# kiibohd_at90usb_ext_i2c_l.net
KiCad netlist of a schematic drawn in EAGLE
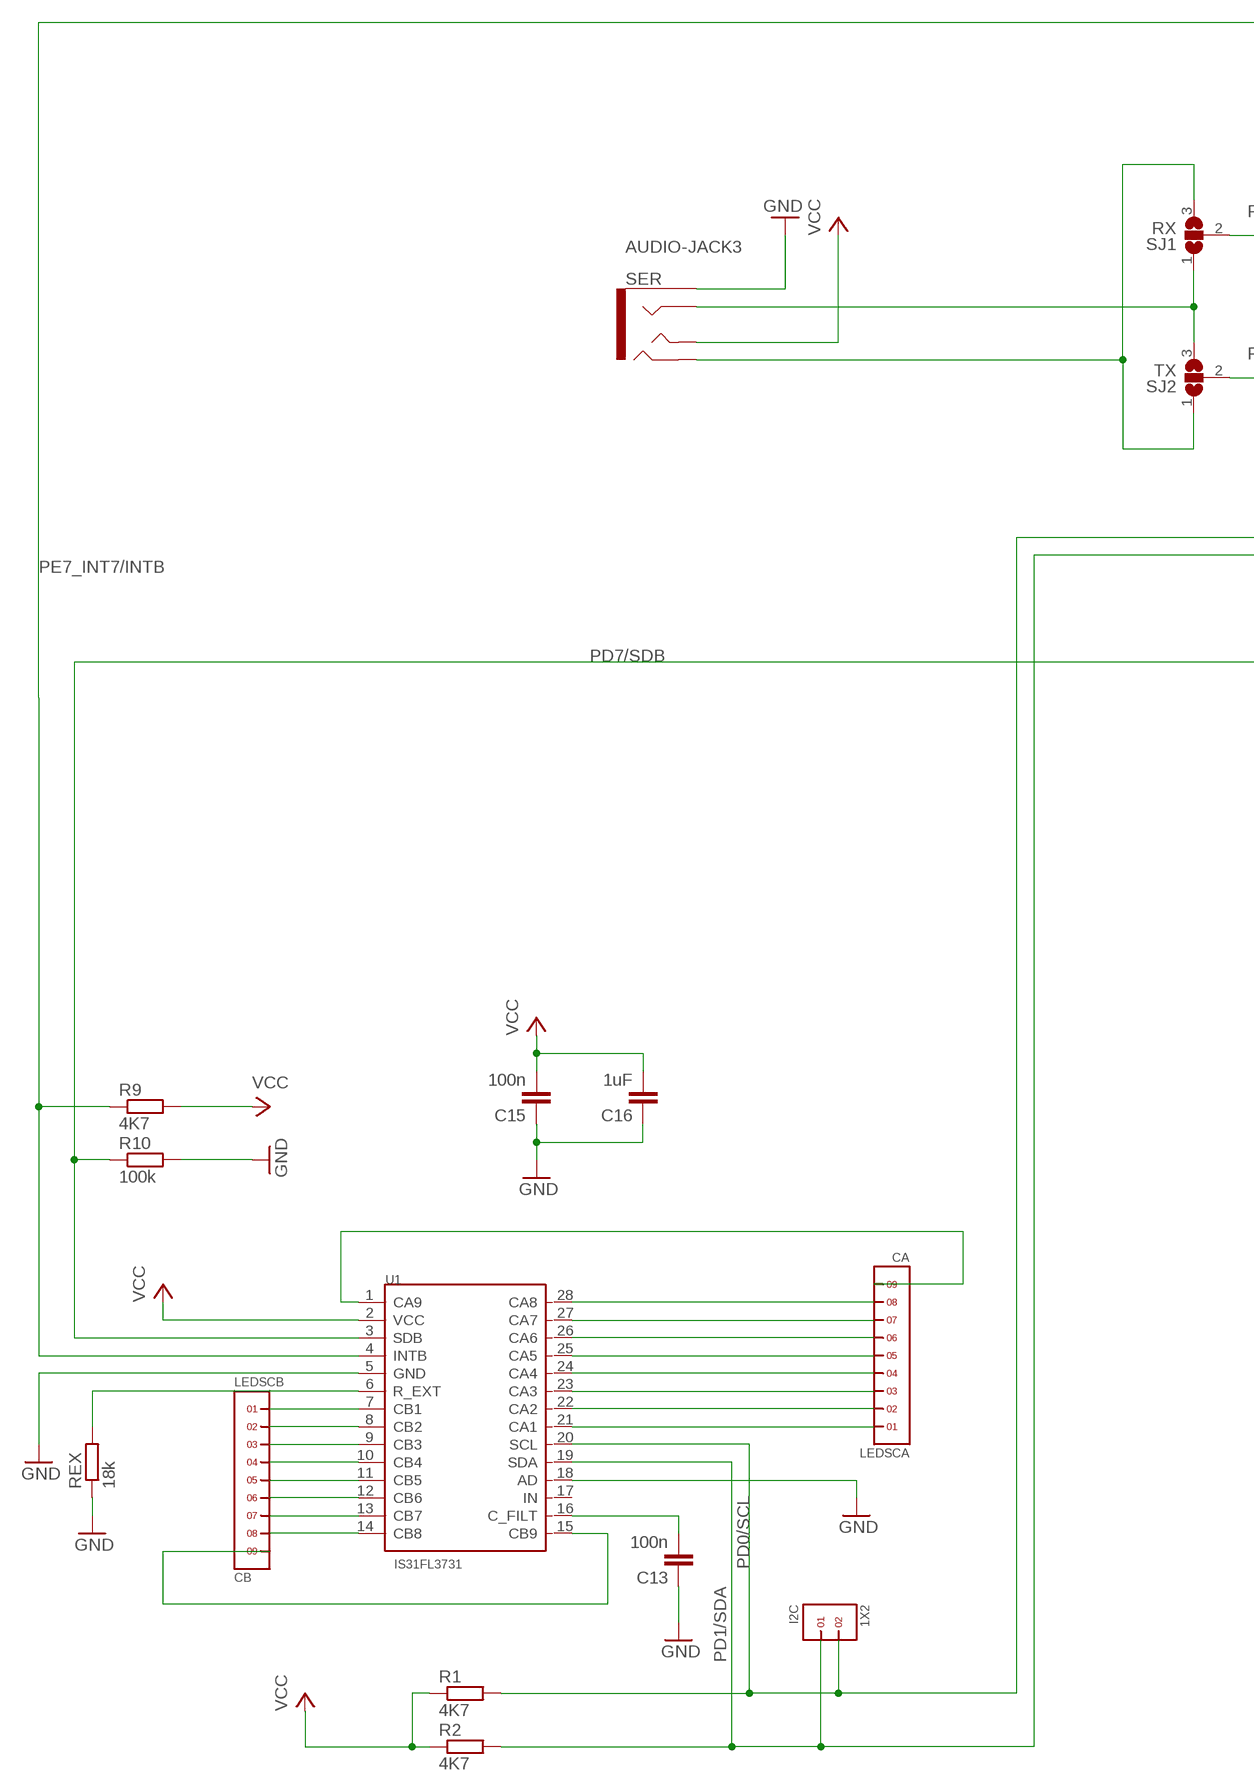
[diagram p0: schematic, sheet 1, part 1 of 2]
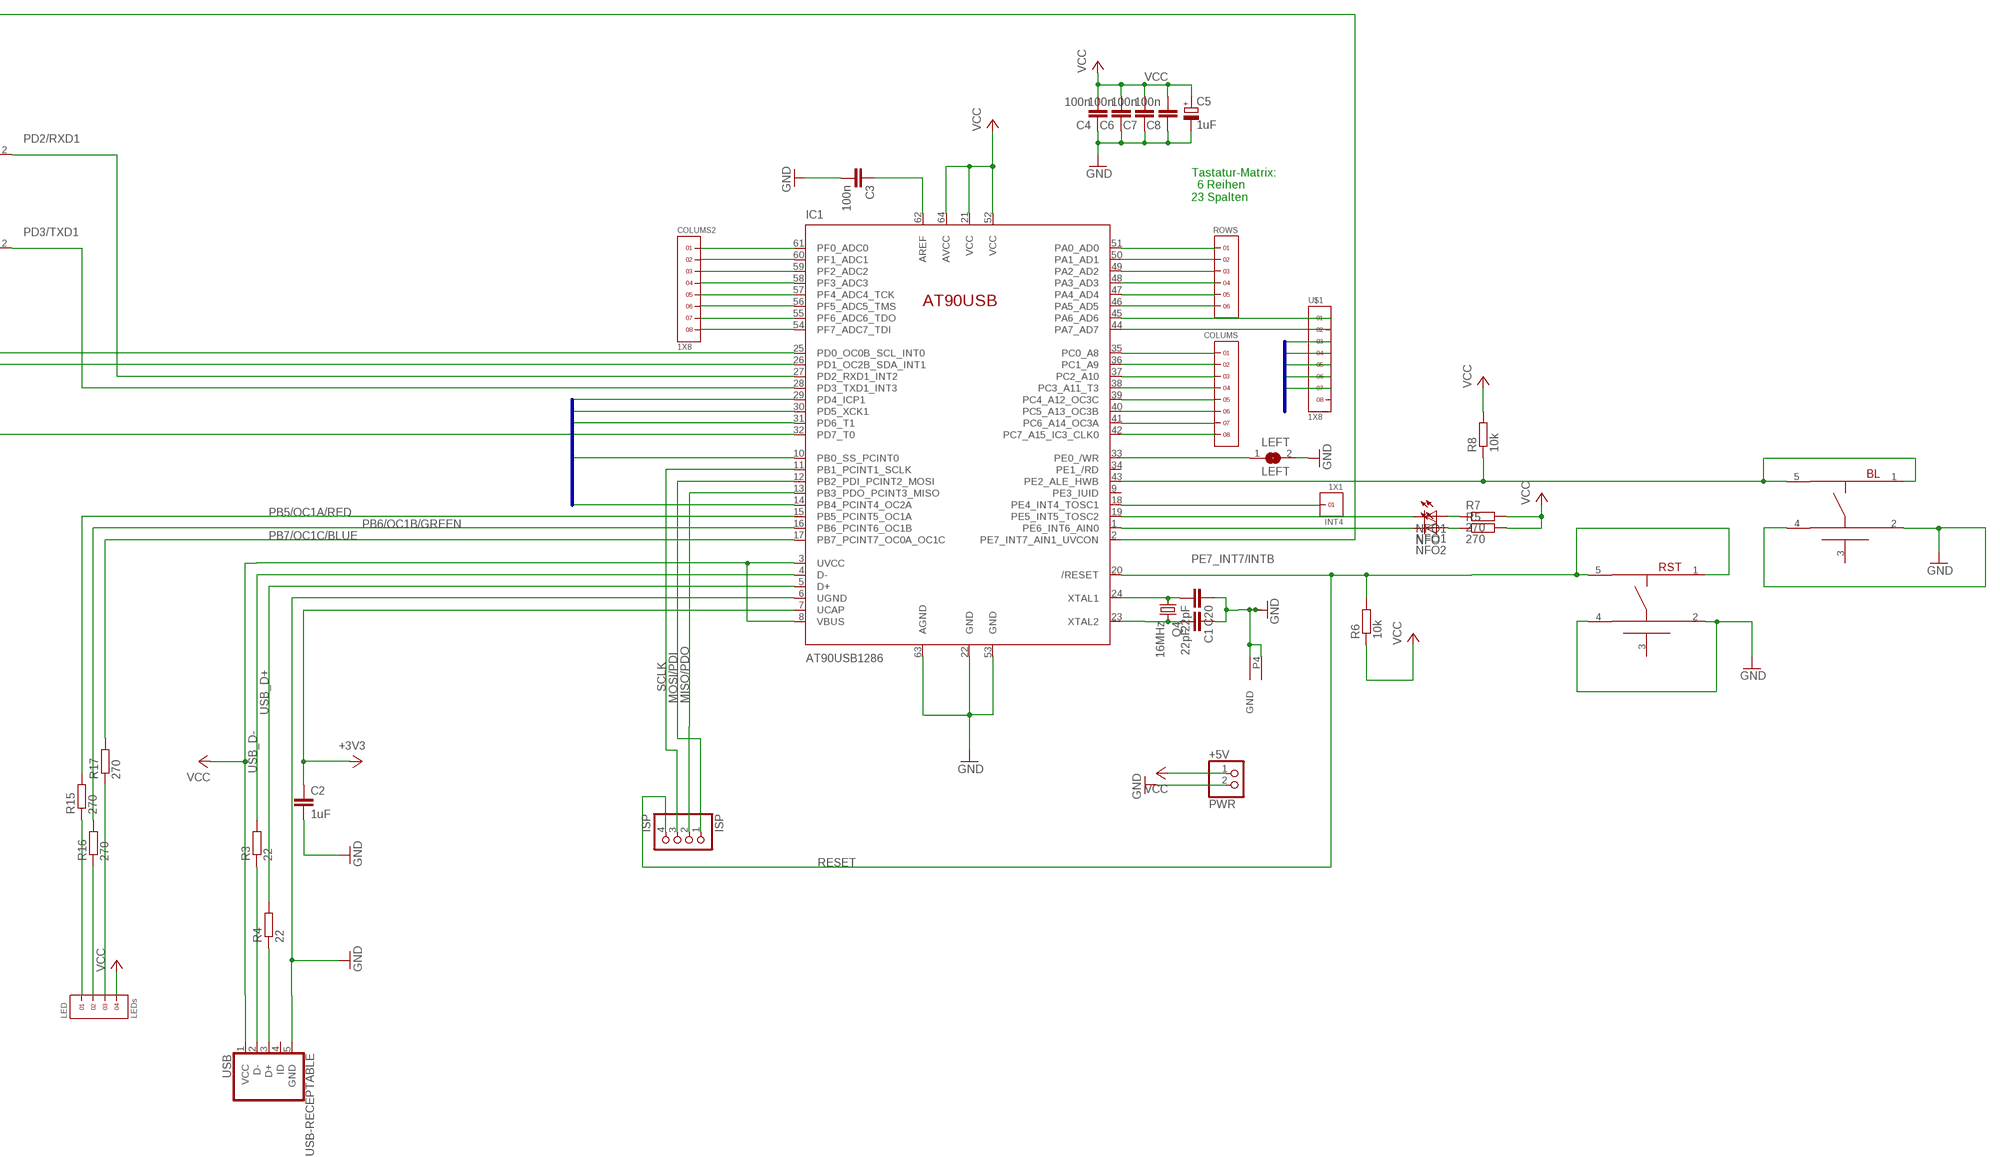
[diagram p1: schematic, sheet 1, part 2 of 2]

(export (version "E")
  (design (tool "Eeschema 10.0.6"))
  (components
    (comp (ref "+5V")
      (value "PWR")
      (footprint "eagle-import:1X02")
      (libsource (lib "eagle-import") (part "PINHD-1X2"))
    )
    (comp (ref "BL")
      (value "KMSXXXG")
      (footprint "eagle-import:C&K-KMS-SWITCH")
      (libsource (lib "eagle-import") (part "KMSXXXG"))
    )
    (comp (ref "C1")
      (value "22pF")
      (footprint "eagle-import:C1206")
      (libsource (lib "eagle-import") (part "C-EUC1206"))
    )
    (comp (ref "C2")
      (value "1uF")
      (footprint "eagle-import:C1206")
      (libsource (lib "eagle-import") (part "C-EUC1206"))
    )
    (comp (ref "C3")
      (value "100n")
      (footprint "eagle-import:C1206")
      (libsource (lib "eagle-import") (part "C-EUC1206"))
    )
    (comp (ref "C4")
      (value "100n")
      (footprint "eagle-import:C1206")
      (libsource (lib "eagle-import") (part "C-EUC1206"))
    )
    (comp (ref "C5")
      (value "1uF")
      (footprint "eagle-import:E2-4")
      (libsource (lib "eagle-import") (part "CPOL-EUE2-4"))
    )
    (comp (ref "C6")
      (value "100n")
      (footprint "eagle-import:C1206")
      (libsource (lib "eagle-import") (part "C-EUC1206"))
    )
    (comp (ref "C7")
      (value "100n")
      (footprint "eagle-import:C1206")
      (libsource (lib "eagle-import") (part "C-EUC1206"))
    )
    (comp (ref "C8")
      (value "100n")
      (footprint "eagle-import:C1206")
      (libsource (lib "eagle-import") (part "C-EUC1206"))
    )
    (comp (ref "C13")
      (value "100n")
      (footprint "eagle-import:C1206")
      (libsource (lib "eagle-import") (part "C-EUC1206"))
    )
    (comp (ref "C15")
      (value "100n")
      (footprint "eagle-import:C1206")
      (libsource (lib "eagle-import") (part "C-EUC1206"))
    )
    (comp (ref "C16")
      (value "1uF")
      (footprint "eagle-import:C1206")
      (libsource (lib "eagle-import") (part "C-EUC1206"))
    )
    (comp (ref "C20")
      (value "22pF")
      (footprint "eagle-import:C1206")
      (libsource (lib "eagle-import") (part "C-EUC1206"))
    )
    (comp (ref "COLUMS")
      (value "1X8")
      (footprint "eagle-import:1X8")
      (libsource (lib "eagle-import") (part "1X8"))
    )
    (comp (ref "COLUMS2")
      (value "1X8")
      (footprint "eagle-import:1X8")
      (libsource (lib "eagle-import") (part "1X8"))
    )
    (comp (ref "I2C")
      (value "1X2")
      (footprint "eagle-import:1X2")
      (libsource (lib "eagle-import") (part "1X2"))
    )
    (comp (ref "IC1")
      (value "AT90USB1286")
      (footprint "eagle-import:TQFP64")
      (libsource (lib "eagle-import") (part "AT90USB-TQFP"))
    )
    (comp (ref "INT4")
      (value "1X1")
      (footprint "eagle-import:1X1")
      (libsource (lib "eagle-import") (part "1X1"))
    )
    (comp (ref "ISP")
      (value "ISP")
      (footprint "eagle-import:1X04")
      (libsource (lib "eagle-import") (part "PINHD-1X4"))
    )
    (comp (ref "LED")
      (value "LEDs")
      (footprint "eagle-import:1X4")
      (libsource (lib "eagle-import") (part "1X4"))
    )
    (comp (ref "LEDSCA")
      (value "CA")
      (footprint "eagle-import:1X9")
      (libsource (lib "eagle-import") (part "1X9"))
    )
    (comp (ref "LEDSCB")
      (value "CB")
      (footprint "eagle-import:1X9")
      (libsource (lib "eagle-import") (part "1X9"))
    )
    (comp (ref "LEFT")
      (value "LEFT")
      (footprint "eagle-import:SJ")
      (libsource (lib "eagle-import") (part "SJ"))
    )
    (comp (ref "NFO")
      (value "NFO2")
      (footprint "eagle-import:CHIP-LED0805")
      (libsource (lib "eagle-import") (part "LEDCHIP-LED0805"))
    )
    (comp (ref "NFO1")
      (value "NFO1")
      (footprint "eagle-import:CHIP-LED0805")
      (libsource (lib "eagle-import") (part "LEDCHIP-LED0805"))
    )
    (comp (ref "Q4")
      (value "16MHz")
      (footprint "eagle-import:MJ")
      (libsource (lib "eagle-import") (part "CRYSTALMJ"))
    )
    (comp (ref "R1")
      (value "4K7")
      (footprint "eagle-import:R1206")
      (libsource (lib "eagle-import") (part "R-EU_R1206"))
    )
    (comp (ref "R2")
      (value "4K7")
      (footprint "eagle-import:R1206")
      (libsource (lib "eagle-import") (part "R-EU_R1206"))
    )
    (comp (ref "R3")
      (value "22")
      (footprint "eagle-import:R1206")
      (libsource (lib "eagle-import") (part "R-EU_R1206"))
    )
    (comp (ref "R4")
      (value "22")
      (footprint "eagle-import:R1206")
      (libsource (lib "eagle-import") (part "R-EU_R1206"))
    )
    (comp (ref "R5")
      (value "270")
      (footprint "eagle-import:R1206")
      (libsource (lib "eagle-import") (part "R-EU_R1206"))
    )
    (comp (ref "R6")
      (value "10k")
      (footprint "eagle-import:R1206")
      (libsource (lib "eagle-import") (part "R-EU_R1206"))
    )
    (comp (ref "R7")
      (value "270")
      (footprint "eagle-import:R1206")
      (libsource (lib "eagle-import") (part "R-EU_R1206"))
    )
    (comp (ref "R8")
      (value "10k")
      (footprint "eagle-import:R1206")
      (libsource (lib "eagle-import") (part "R-EU_R1206"))
    )
    (comp (ref "R9")
      (value "4K7")
      (footprint "eagle-import:R1206")
      (libsource (lib "eagle-import") (part "R-EU_R1206"))
    )
    (comp (ref "R10")
      (value "100k")
      (footprint "eagle-import:R1206")
      (libsource (lib "eagle-import") (part "R-EU_R1206"))
    )
    (comp (ref "R15")
      (value "270")
      (footprint "eagle-import:R1206")
      (libsource (lib "eagle-import") (part "R-EU_R1206"))
    )
    (comp (ref "R16")
      (value "270")
      (footprint "eagle-import:R1206")
      (libsource (lib "eagle-import") (part "R-EU_R1206"))
    )
    (comp (ref "R17")
      (value "270")
      (footprint "eagle-import:R1206")
      (libsource (lib "eagle-import") (part "R-EU_R1206"))
    )
    (comp (ref "REX")
      (value "18k")
      (footprint "eagle-import:R1206")
      (libsource (lib "eagle-import") (part "R-EU_R1206"))
    )
    (comp (ref "ROWS")
      (value "1X6")
      (footprint "eagle-import:1X6")
      (libsource (lib "eagle-import") (part "1X6"))
    )
    (comp (ref "RST")
      (value "KMSXXXG")
      (footprint "eagle-import:C&K-KMS-SWITCH")
      (libsource (lib "eagle-import") (part "KMSXXXG"))
    )
    (comp (ref "SER")
      (value "AUDIO-JACK3")
      (footprint "eagle-import:AUDIO-JACK-TRRS-SMD")
      (libsource (lib "eagle-import") (part "AUDIO-JACK3"))
    )
    (comp (ref "SJ1")
      (value "RX")
      (footprint "eagle-import:SJ_2")
      (libsource (lib "eagle-import") (part "SJ2W"))
    )
    (comp (ref "SJ2")
      (value "TX")
      (footprint "eagle-import:SJ_2")
      (libsource (lib "eagle-import") (part "SJ2W"))
    )
    (comp (ref "U$1")
      (value "1X8")
      (footprint "eagle-import:1X8")
      (libsource (lib "eagle-import") (part "1X8"))
    )
    (comp (ref "U1")
      (value "IS31FL3731")
      (footprint "eagle-import:SSOP28-0.65-10.2X5.2MM")
      (fields (field (name "MPN") "WM8731SEDS/V"))
      (libsource (lib "eagle-import") (part "IS31FL3731(SSOP28)"))
    )
    (comp (ref "USB")
      (value "USB-RECEPTABLE")
      (footprint "eagle-import:FCI-10103594-0001LF")
      (libsource (lib "eagle-import") (part "USB-RECEPTABLE"))
    )
  )
  (nets
    (net (code "1") (name "+3V3") (class "Default")
      (node (ref "C2") (pin "1") (pinfunction "1_1") (pintype "passive"))
      (node (ref "IC1") (pin "7") (pinfunction "UCAP_7") (pintype "power_in"))
    )
    (net (code "2") (name "/MISO{slash}PDO") (class "Default")
      (node (ref "IC1") (pin "13") (pinfunction "PB3_PDO_PCINT3_MISO_13") (pintype "bidirectional"))
      (node (ref "ISP") (pin "2") (pinfunction "2_2") (pintype "passive"))
    )
    (net (code "3") (name "/MOSI{slash}PDI") (class "Default")
      (node (ref "IC1") (pin "12") (pinfunction "PB2_PDI_PCINT2_MOSI_12") (pintype "bidirectional"))
      (node (ref "ISP") (pin "1") (pinfunction "1_1") (pintype "passive"))
    )
    (net (code "4") (name "/PB0") (class "Default")
      (node (ref "IC1") (pin "10") (pinfunction "PB0_SS_PCINT0_10") (pintype "bidirectional"))
      (node (ref "U$1") (pin "6") (pinfunction "6_6") (pintype "bidirectional"))
    )
    (net (code "5") (name "/PB4") (class "Default")
      (node (ref "IC1") (pin "14") (pinfunction "PB4_PCINT4_OC2A_14") (pintype "bidirectional"))
      (node (ref "U$1") (pin "7") (pinfunction "7_7") (pintype "bidirectional"))
    )
    (net (code "6") (name "/PB5{slash}OC1A{slash}RED") (class "Default")
      (node (ref "IC1") (pin "15") (pinfunction "PB5_PCINT5_OC1A_15") (pintype "bidirectional"))
      (node (ref "R15") (pin "2") (pinfunction "2_2") (pintype "passive"))
    )
    (net (code "7") (name "/PB6{slash}OC1B{slash}GREEN") (class "Default")
      (node (ref "IC1") (pin "16") (pinfunction "PB6_PCINT6_OC1B_16") (pintype "bidirectional"))
      (node (ref "R16") (pin "2") (pinfunction "2_2") (pintype "passive"))
    )
    (net (code "8") (name "/PB7{slash}OC1C{slash}BLUE") (class "Default")
      (node (ref "IC1") (pin "17") (pinfunction "PB7_PCINT7_OC0A_OC1C_17") (pintype "bidirectional"))
      (node (ref "R17") (pin "2") (pinfunction "2_2") (pintype "passive"))
    )
    (net (code "9") (name "/PD0{slash}SCL") (class "Default")
      (node (ref "I2C") (pin "2") (pinfunction "2_2") (pintype "bidirectional"))
      (node (ref "IC1") (pin "25") (pinfunction "PD0_OC0B_SCL_INT0_25") (pintype "bidirectional"))
      (node (ref "R1") (pin "2") (pinfunction "2_2") (pintype "passive"))
      (node (ref "U1") (pin "20") (pinfunction "SCL_20") (pintype "bidirectional"))
    )
    (net (code "10") (name "/PD1{slash}SDA") (class "Default")
      (node (ref "I2C") (pin "1") (pinfunction "1_1") (pintype "bidirectional"))
      (node (ref "IC1") (pin "26") (pinfunction "PD1_OC2B_SDA_INT1_26") (pintype "bidirectional"))
      (node (ref "R2") (pin "2") (pinfunction "2_2") (pintype "passive"))
      (node (ref "U1") (pin "19") (pinfunction "SDA_19") (pintype "bidirectional"))
    )
    (net (code "11") (name "/PD2{slash}RXD1") (class "Default")
      (node (ref "IC1") (pin "27") (pinfunction "PD2_RXD1_INT2_27") (pintype "bidirectional"))
      (node (ref "SJ1") (pin "2") (pinfunction "2_2") (pintype "passive"))
    )
    (net (code "12") (name "/PD3{slash}TXD1") (class "Default")
      (node (ref "IC1") (pin "28") (pinfunction "PD3_TXD1_INT3_28") (pintype "bidirectional"))
      (node (ref "SJ2") (pin "2") (pinfunction "2_2") (pintype "passive"))
    )
    (net (code "13") (name "/PD4") (class "Default")
      (node (ref "IC1") (pin "29") (pinfunction "PD4_ICP1_29") (pintype "bidirectional"))
      (node (ref "U$1") (pin "3") (pinfunction "3_3") (pintype "bidirectional"))
    )
    (net (code "14") (name "/PD5") (class "Default")
      (node (ref "IC1") (pin "30") (pinfunction "PD5_XCK1_30") (pintype "bidirectional"))
      (node (ref "U$1") (pin "4") (pinfunction "4_4") (pintype "bidirectional"))
    )
    (net (code "15") (name "/PD6") (class "Default")
      (node (ref "IC1") (pin "31") (pinfunction "PD6_T1_31") (pintype "bidirectional"))
      (node (ref "U$1") (pin "5") (pinfunction "5_5") (pintype "bidirectional"))
    )
    (net (code "16") (name "/PD7{slash}SDB") (class "Default")
      (node (ref "IC1") (pin "32") (pinfunction "PD7_T0_32") (pintype "bidirectional"))
      (node (ref "R10") (pin "1") (pinfunction "1_1") (pintype "passive"))
      (node (ref "U1") (pin "3") (pinfunction "SDB_3") (pintype "bidirectional"))
    )
    (net (code "17") (name "/PE7_INT7{slash}INTB") (class "Default")
      (node (ref "IC1") (pin "2") (pinfunction "PE7_INT7_AIN1_UVCON_2") (pintype "bidirectional"))
      (node (ref "R9") (pin "1") (pinfunction "1_1") (pintype "passive"))
      (node (ref "U1") (pin "4") (pinfunction "INTB_4") (pintype "bidirectional"))
    )
    (net (code "18") (name "/RESET") (class "Default")
      (node (ref "IC1") (pin "20") (pinfunction "/RESET_20") (pintype "bidirectional"))
      (node (ref "ISP") (pin "4") (pinfunction "4_4") (pintype "passive"))
      (node (ref "R6") (pin "2") (pinfunction "2_2") (pintype "passive"))
      (node (ref "RST") (pin "1") (pinfunction "1_1") (pintype "bidirectional"))
      (node (ref "RST") (pin "5") (pinfunction "5_5") (pintype "bidirectional"))
    )
    (net (code "19") (name "/SCLK") (class "Default")
      (node (ref "IC1") (pin "11") (pinfunction "PB1_PCINT1_SCLK_11") (pintype "bidirectional"))
      (node (ref "ISP") (pin "3") (pinfunction "3_3") (pintype "passive"))
    )
    (net (code "20") (name "/USB_D+") (class "Default")
      (node (ref "IC1") (pin "5") (pinfunction "D+_5") (pintype "bidirectional"))
      (node (ref "R4") (pin "2") (pinfunction "2_2") (pintype "passive"))
    )
    (net (code "21") (name "/USB_D-") (class "Default")
      (node (ref "IC1") (pin "4") (pinfunction "D-_4") (pintype "bidirectional"))
      (node (ref "R3") (pin "2") (pinfunction "2_2") (pintype "passive"))
    )
    (net (code "22") (name "GND") (class "Default")
      (node (ref "+5V") (pin "2") (pinfunction "2_2") (pintype "passive"))
      (node (ref "BL") (pin "2") (pinfunction "2_2") (pintype "bidirectional"))
      (node (ref "BL") (pin "4") (pinfunction "4_4") (pintype "bidirectional"))
      (node (ref "C1") (pin "1") (pinfunction "1_1") (pintype "passive"))
      (node (ref "C13") (pin "1") (pinfunction "1_1") (pintype "passive"))
      (node (ref "C15") (pin "1") (pinfunction "1_1") (pintype "passive"))
      (node (ref "C16") (pin "1") (pinfunction "1_1") (pintype "passive"))
      (node (ref "C2") (pin "2") (pinfunction "2_2") (pintype "passive"))
      (node (ref "C20") (pin "1") (pinfunction "1_1") (pintype "passive"))
      (node (ref "C3") (pin "2") (pinfunction "2_2") (pintype "passive"))
      (node (ref "C4") (pin "1") (pinfunction "1_1") (pintype "passive"))
      (node (ref "C5") (pin "-") (pinfunction "-_-") (pintype "passive"))
      (node (ref "C6") (pin "1") (pinfunction "1_1") (pintype "passive"))
      (node (ref "C7") (pin "1") (pinfunction "1_1") (pintype "passive"))
      (node (ref "C8") (pin "1") (pinfunction "1_1") (pintype "passive"))
      (node (ref "IC1") (pin "22") (pinfunction "GND_22") (pintype "power_in"))
      (node (ref "IC1") (pin "53") (pinfunction "GND_53") (pintype "power_in"))
      (node (ref "IC1") (pin "6") (pinfunction "UGND_6") (pintype "power_in"))
      (node (ref "IC1") (pin "63") (pinfunction "AGND_63") (pintype "power_in"))
      (node (ref "LEFT") (pin "2") (pinfunction "2_2") (pintype "passive"))
      (node (ref "Q4") (pin "P2") (pinfunction "GND_P2") (pintype "bidirectional"))
      (node (ref "Q4") (pin "P4") (pinfunction "GND1_P4") (pintype "bidirectional"))
      (node (ref "R10") (pin "2") (pinfunction "2_2") (pintype "passive"))
      (node (ref "REX") (pin "1") (pinfunction "1_1") (pintype "passive"))
      (node (ref "RST") (pin "2") (pinfunction "2_2") (pintype "bidirectional"))
      (node (ref "RST") (pin "4") (pinfunction "4_4") (pintype "bidirectional"))
      (node (ref "SER") (pin "EARTH") (pinfunction "EARTH_EARTH") (pintype "bidirectional"))
      (node (ref "U1") (pin "18") (pinfunction "AD_18") (pintype "bidirectional"))
      (node (ref "U1") (pin "5") (pinfunction "GND_5") (pintype "power_in"))
      (node (ref "USB") (pin "5") (pinfunction "GND_5") (pintype "bidirectional"))
    )
    (net (code "23") (name "Net-(IC1-AREF)") (class "Default")
      (node (ref "C3") (pin "1") (pinfunction "1_1") (pintype "passive"))
      (node (ref "IC1") (pin "62") (pinfunction "AREF_62") (pintype "power_in"))
    )
    (net (code "24") (name "Net-(IC1-PA0_AD0)") (class "Default")
      (node (ref "IC1") (pin "51") (pinfunction "PA0_AD0_51") (pintype "bidirectional"))
      (node (ref "ROWS") (pin "1") (pinfunction "1_1") (pintype "bidirectional"))
    )
    (net (code "25") (name "Net-(IC1-PA1_AD1)") (class "Default")
      (node (ref "IC1") (pin "50") (pinfunction "PA1_AD1_50") (pintype "bidirectional"))
      (node (ref "ROWS") (pin "2") (pinfunction "2_2") (pintype "bidirectional"))
    )
    (net (code "26") (name "Net-(IC1-PA2_AD2)") (class "Default")
      (node (ref "IC1") (pin "49") (pinfunction "PA2_AD2_49") (pintype "bidirectional"))
      (node (ref "ROWS") (pin "3") (pinfunction "3_3") (pintype "bidirectional"))
    )
    (net (code "27") (name "Net-(IC1-PA3_AD3)") (class "Default")
      (node (ref "IC1") (pin "48") (pinfunction "PA3_AD3_48") (pintype "bidirectional"))
      (node (ref "ROWS") (pin "4") (pinfunction "4_4") (pintype "bidirectional"))
    )
    (net (code "28") (name "Net-(IC1-PA4_AD4)") (class "Default")
      (node (ref "IC1") (pin "47") (pinfunction "PA4_AD4_47") (pintype "bidirectional"))
      (node (ref "ROWS") (pin "5") (pinfunction "5_5") (pintype "bidirectional"))
    )
    (net (code "29") (name "Net-(IC1-PA5_AD5)") (class "Default")
      (node (ref "IC1") (pin "46") (pinfunction "PA5_AD5_46") (pintype "bidirectional"))
      (node (ref "ROWS") (pin "6") (pinfunction "6_6") (pintype "bidirectional"))
    )
    (net (code "30") (name "Net-(IC1-PA6_AD6)") (class "Default")
      (node (ref "IC1") (pin "45") (pinfunction "PA6_AD6_45") (pintype "bidirectional"))
      (node (ref "U$1") (pin "1") (pinfunction "1_1") (pintype "bidirectional"))
    )
    (net (code "31") (name "Net-(IC1-PA7_AD7)") (class "Default")
      (node (ref "IC1") (pin "44") (pinfunction "PA7_AD7_44") (pintype "bidirectional"))
      (node (ref "U$1") (pin "2") (pinfunction "2_2") (pintype "bidirectional"))
    )
    (net (code "32") (name "Net-(IC1-PC0_A8)") (class "Default")
      (node (ref "COLUMS") (pin "1") (pinfunction "1_1") (pintype "bidirectional"))
      (node (ref "IC1") (pin "35") (pinfunction "PC0_A8_35") (pintype "bidirectional"))
    )
    (net (code "33") (name "Net-(IC1-PC1_A9)") (class "Default")
      (node (ref "COLUMS") (pin "2") (pinfunction "2_2") (pintype "bidirectional"))
      (node (ref "IC1") (pin "36") (pinfunction "PC1_A9_36") (pintype "bidirectional"))
    )
    (net (code "34") (name "Net-(IC1-PC2_A10)") (class "Default")
      (node (ref "COLUMS") (pin "3") (pinfunction "3_3") (pintype "bidirectional"))
      (node (ref "IC1") (pin "37") (pinfunction "PC2_A10_37") (pintype "bidirectional"))
    )
    (net (code "35") (name "Net-(IC1-PC3_A11_T3)") (class "Default")
      (node (ref "COLUMS") (pin "4") (pinfunction "4_4") (pintype "bidirectional"))
      (node (ref "IC1") (pin "38") (pinfunction "PC3_A11_T3_38") (pintype "bidirectional"))
    )
    (net (code "36") (name "Net-(IC1-PC4_A12_OC3C)") (class "Default")
      (node (ref "COLUMS") (pin "5") (pinfunction "5_5") (pintype "bidirectional"))
      (node (ref "IC1") (pin "39") (pinfunction "PC4_A12_OC3C_39") (pintype "bidirectional"))
    )
    (net (code "37") (name "Net-(IC1-PC5_A13_OC3B)") (class "Default")
      (node (ref "COLUMS") (pin "6") (pinfunction "6_6") (pintype "bidirectional"))
      (node (ref "IC1") (pin "40") (pinfunction "PC5_A13_OC3B_40") (pintype "bidirectional"))
    )
    (net (code "38") (name "Net-(IC1-PC6_A14_OC3A)") (class "Default")
      (node (ref "COLUMS") (pin "7") (pinfunction "7_7") (pintype "bidirectional"))
      (node (ref "IC1") (pin "41") (pinfunction "PC6_A14_OC3A_41") (pintype "bidirectional"))
    )
    (net (code "39") (name "Net-(IC1-PC7_A15_IC3_CLK0)") (class "Default")
      (node (ref "COLUMS") (pin "8") (pinfunction "8_8") (pintype "bidirectional"))
      (node (ref "IC1") (pin "42") (pinfunction "PC7_A15_IC3_CLK0_42") (pintype "bidirectional"))
    )
    (net (code "40") (name "Net-(IC1-PE0_{slash}WR)") (class "Default")
      (node (ref "IC1") (pin "33") (pinfunction "PE0_/WR_33") (pintype "bidirectional"))
      (node (ref "LEFT") (pin "1") (pinfunction "1_1") (pintype "passive"))
    )
    (net (code "41") (name "Net-(IC1-PE2_ALE_HWB)") (class "Default")
      (node (ref "BL") (pin "1") (pinfunction "1_1") (pintype "bidirectional"))
      (node (ref "BL") (pin "5") (pinfunction "5_5") (pintype "bidirectional"))
      (node (ref "IC1") (pin "43") (pinfunction "PE2_ALE_HWB_43") (pintype "bidirectional"))
      (node (ref "R8") (pin "1") (pinfunction "1_1") (pintype "passive"))
    )
    (net (code "42") (name "Net-(IC1-PE4_INT4_TOSC1)") (class "Default")
      (node (ref "IC1") (pin "18") (pinfunction "PE4_INT4_TOSC1_18") (pintype "bidirectional"))
      (node (ref "INT4") (pin "1") (pinfunction "1_1") (pintype "bidirectional"))
    )
    (net (code "43") (name "Net-(IC1-PE5_INT5_TOSC2)") (class "Default")
      (node (ref "IC1") (pin "19") (pinfunction "PE5_INT5_TOSC2_19") (pintype "bidirectional"))
      (node (ref "NFO1") (pin "C") (pinfunction "C_C") (pintype "passive"))
    )
    (net (code "44") (name "Net-(IC1-PE6_INT6_AIN0)") (class "Default")
      (node (ref "IC1") (pin "1") (pinfunction "PE6_INT6_AIN0_1") (pintype "bidirectional"))
      (node (ref "NFO") (pin "C") (pinfunction "C_C") (pintype "passive"))
    )
    (net (code "45") (name "Net-(IC1-PF0_ADC0)") (class "Default")
      (node (ref "COLUMS2") (pin "1") (pinfunction "1_1") (pintype "bidirectional"))
      (node (ref "IC1") (pin "61") (pinfunction "PF0_ADC0_61") (pintype "bidirectional"))
    )
    (net (code "46") (name "Net-(IC1-PF1_ADC1)") (class "Default")
      (node (ref "COLUMS2") (pin "2") (pinfunction "2_2") (pintype "bidirectional"))
      (node (ref "IC1") (pin "60") (pinfunction "PF1_ADC1_60") (pintype "bidirectional"))
    )
    (net (code "47") (name "Net-(IC1-PF2_ADC2)") (class "Default")
      (node (ref "COLUMS2") (pin "3") (pinfunction "3_3") (pintype "bidirectional"))
      (node (ref "IC1") (pin "59") (pinfunction "PF2_ADC2_59") (pintype "bidirectional"))
    )
    (net (code "48") (name "Net-(IC1-PF3_ADC3)") (class "Default")
      (node (ref "COLUMS2") (pin "4") (pinfunction "4_4") (pintype "bidirectional"))
      (node (ref "IC1") (pin "58") (pinfunction "PF3_ADC3_58") (pintype "bidirectional"))
    )
    (net (code "49") (name "Net-(IC1-PF4_ADC4_TCK)") (class "Default")
      (node (ref "COLUMS2") (pin "5") (pinfunction "5_5") (pintype "bidirectional"))
      (node (ref "IC1") (pin "57") (pinfunction "PF4_ADC4_TCK_57") (pintype "bidirectional"))
    )
    (net (code "50") (name "Net-(IC1-PF5_ADC5_TMS)") (class "Default")
      (node (ref "COLUMS2") (pin "6") (pinfunction "6_6") (pintype "bidirectional"))
      (node (ref "IC1") (pin "56") (pinfunction "PF5_ADC5_TMS_56") (pintype "bidirectional"))
    )
    (net (code "51") (name "Net-(IC1-PF6_ADC6_TDO)") (class "Default")
      (node (ref "COLUMS2") (pin "7") (pinfunction "7_7") (pintype "bidirectional"))
      (node (ref "IC1") (pin "55") (pinfunction "PF6_ADC6_TDO_55") (pintype "bidirectional"))
    )
    (net (code "52") (name "Net-(IC1-PF7_ADC7_TDI)") (class "Default")
      (node (ref "COLUMS2") (pin "8") (pinfunction "8_8") (pintype "bidirectional"))
      (node (ref "IC1") (pin "54") (pinfunction "PF7_ADC7_TDI_54") (pintype "bidirectional"))
    )
    (net (code "53") (name "Net-(IC1-XTAL1)") (class "Default")
      (node (ref "C20") (pin "2") (pinfunction "2_2") (pintype "passive"))
      (node (ref "IC1") (pin "24") (pinfunction "XTAL1_24") (pintype "passive"))
      (node (ref "Q4") (pin "P1") (pinfunction "1_P1") (pintype "passive"))
    )
    (net (code "54") (name "Net-(IC1-XTAL2)") (class "Default")
      (node (ref "C1") (pin "2") (pinfunction "2_2") (pintype "passive"))
      (node (ref "IC1") (pin "23") (pinfunction "XTAL2_23") (pintype "passive"))
      (node (ref "Q4") (pin "P3") (pinfunction "2_P3") (pintype "passive"))
    )
    (net (code "55") (name "Net-(LED-Pad1)") (class "Default")
      (node (ref "LED") (pin "1") (pinfunction "1_1") (pintype "bidirectional"))
      (node (ref "R15") (pin "1") (pinfunction "1_1") (pintype "passive"))
    )
    (net (code "56") (name "Net-(LED-Pad2)") (class "Default")
      (node (ref "LED") (pin "2") (pinfunction "2_2") (pintype "bidirectional"))
      (node (ref "R16") (pin "1") (pinfunction "1_1") (pintype "passive"))
    )
    (net (code "57") (name "Net-(LED-Pad3)") (class "Default")
      (node (ref "LED") (pin "3") (pinfunction "3_3") (pintype "bidirectional"))
      (node (ref "R17") (pin "1") (pinfunction "1_1") (pintype "passive"))
    )
    (net (code "58") (name "Net-(NFO-PadA)") (class "Default")
      (node (ref "NFO") (pin "A") (pinfunction "A_A") (pintype "passive"))
      (node (ref "R5") (pin "1") (pinfunction "1_1") (pintype "passive"))
    )
    (net (code "59") (name "Net-(NFO1-PadA)") (class "Default")
      (node (ref "NFO1") (pin "A") (pinfunction "A_A") (pintype "passive"))
      (node (ref "R7") (pin "1") (pinfunction "1_1") (pintype "passive"))
    )
    (net (code "60") (name "Net-(SER-PadRING1)") (class "Default")
      (node (ref "SER") (pin "RING1") (pinfunction "RING1_RING1") (pintype "bidirectional"))
      (node (ref "SJ1") (pin "1") (pinfunction "1_1") (pintype "passive"))
      (node (ref "SJ2") (pin "3") (pinfunction "3_3") (pintype "passive"))
    )
    (net (code "61") (name "Net-(SER-PadRING2)") (class "Default")
      (node (ref "SER") (pin "RING2") (pinfunction "RING2_RING2") (pintype "bidirectional"))
      (node (ref "SJ1") (pin "3") (pinfunction "3_3") (pintype "passive"))
      (node (ref "SJ2") (pin "1") (pinfunction "1_1") (pintype "passive"))
    )
    (net (code "62") (name "Net-(U1-CA1)") (class "Default")
      (node (ref "LEDSCA") (pin "1") (pinfunction "1_1") (pintype "bidirectional"))
      (node (ref "U1") (pin "21") (pinfunction "CA1_21") (pintype "bidirectional"))
    )
    (net (code "63") (name "Net-(U1-CA2)") (class "Default")
      (node (ref "LEDSCA") (pin "2") (pinfunction "2_2") (pintype "bidirectional"))
      (node (ref "U1") (pin "22") (pinfunction "CA2_22") (pintype "bidirectional"))
    )
    (net (code "64") (name "Net-(U1-CA3)") (class "Default")
      (node (ref "LEDSCA") (pin "3") (pinfunction "3_3") (pintype "bidirectional"))
      (node (ref "U1") (pin "23") (pinfunction "CA3_23") (pintype "bidirectional"))
    )
    (net (code "65") (name "Net-(U1-CA4)") (class "Default")
      (node (ref "LEDSCA") (pin "4") (pinfunction "4_4") (pintype "bidirectional"))
      (node (ref "U1") (pin "24") (pinfunction "CA4_24") (pintype "bidirectional"))
    )
    (net (code "66") (name "Net-(U1-CA5)") (class "Default")
      (node (ref "LEDSCA") (pin "5") (pinfunction "5_5") (pintype "bidirectional"))
      (node (ref "U1") (pin "25") (pinfunction "CA5_25") (pintype "bidirectional"))
    )
    (net (code "67") (name "Net-(U1-CA6)") (class "Default")
      (node (ref "LEDSCA") (pin "6") (pinfunction "6_6") (pintype "bidirectional"))
      (node (ref "U1") (pin "26") (pinfunction "CA6_26") (pintype "bidirectional"))
    )
    (net (code "68") (name "Net-(U1-CA7)") (class "Default")
      (node (ref "LEDSCA") (pin "7") (pinfunction "7_7") (pintype "bidirectional"))
      (node (ref "U1") (pin "27") (pinfunction "CA7_27") (pintype "bidirectional"))
    )
    (net (code "69") (name "Net-(U1-CA8)") (class "Default")
      (node (ref "LEDSCA") (pin "8") (pinfunction "8_8") (pintype "bidirectional"))
      (node (ref "U1") (pin "28") (pinfunction "CA8_28") (pintype "bidirectional"))
    )
    (net (code "70") (name "Net-(U1-CA9)") (class "Default")
      (node (ref "LEDSCA") (pin "9") (pinfunction "9_9") (pintype "bidirectional"))
      (node (ref "U1") (pin "1") (pinfunction "CA9_1") (pintype "bidirectional"))
    )
    (net (code "71") (name "Net-(U1-CB1)") (class "Default")
      (node (ref "LEDSCB") (pin "1") (pinfunction "1_1") (pintype "bidirectional"))
      (node (ref "U1") (pin "7") (pinfunction "CB1_7") (pintype "bidirectional"))
    )
    (net (code "72") (name "Net-(U1-CB2)") (class "Default")
      (node (ref "LEDSCB") (pin "2") (pinfunction "2_2") (pintype "bidirectional"))
      (node (ref "U1") (pin "8") (pinfunction "CB2_8") (pintype "bidirectional"))
    )
    (net (code "73") (name "Net-(U1-CB3)") (class "Default")
      (node (ref "LEDSCB") (pin "3") (pinfunction "3_3") (pintype "bidirectional"))
      (node (ref "U1") (pin "9") (pinfunction "CB3_9") (pintype "bidirectional"))
    )
    (net (code "74") (name "Net-(U1-CB4)") (class "Default")
      (node (ref "LEDSCB") (pin "4") (pinfunction "4_4") (pintype "bidirectional"))
      (node (ref "U1") (pin "10") (pinfunction "CB4_10") (pintype "bidirectional"))
    )
    (net (code "75") (name "Net-(U1-CB5)") (class "Default")
      (node (ref "LEDSCB") (pin "5") (pinfunction "5_5") (pintype "bidirectional"))
      (node (ref "U1") (pin "11") (pinfunction "CB5_11") (pintype "bidirectional"))
    )
    (net (code "76") (name "Net-(U1-CB6)") (class "Default")
      (node (ref "LEDSCB") (pin "6") (pinfunction "6_6") (pintype "bidirectional"))
      (node (ref "U1") (pin "12") (pinfunction "CB6_12") (pintype "bidirectional"))
    )
    (net (code "77") (name "Net-(U1-CB7)") (class "Default")
      (node (ref "LEDSCB") (pin "7") (pinfunction "7_7") (pintype "bidirectional"))
      (node (ref "U1") (pin "13") (pinfunction "CB7_13") (pintype "bidirectional"))
    )
    (net (code "78") (name "Net-(U1-CB8)") (class "Default")
      (node (ref "LEDSCB") (pin "8") (pinfunction "8_8") (pintype "bidirectional"))
      (node (ref "U1") (pin "14") (pinfunction "CB8_14") (pintype "bidirectional"))
    )
    (net (code "79") (name "Net-(U1-CB9)") (class "Default")
      (node (ref "LEDSCB") (pin "9") (pinfunction "9_9") (pintype "bidirectional"))
      (node (ref "U1") (pin "15") (pinfunction "CB9_15") (pintype "bidirectional"))
    )
    (net (code "80") (name "Net-(U1-C_FILT)") (class "Default")
      (node (ref "C13") (pin "2") (pinfunction "2_2") (pintype "passive"))
      (node (ref "U1") (pin "16") (pinfunction "C_FILT_16") (pintype "bidirectional"))
    )
    (net (code "81") (name "Net-(U1-R_EXT)") (class "Default")
      (node (ref "REX") (pin "2") (pinfunction "2_2") (pintype "passive"))
      (node (ref "U1") (pin "6") (pinfunction "R_EXT_6") (pintype "bidirectional"))
    )
    (net (code "82") (name "Net-(USB-D+)") (class "Default")
      (node (ref "R4") (pin "1") (pinfunction "1_1") (pintype "passive"))
      (node (ref "USB") (pin "3") (pinfunction "D+_3") (pintype "bidirectional"))
    )
    (net (code "83") (name "Net-(USB-D-)") (class "Default")
      (node (ref "R3") (pin "1") (pinfunction "1_1") (pintype "passive"))
      (node (ref "USB") (pin "2") (pinfunction "D-_2") (pintype "bidirectional"))
    )
    (net (code "84") (name "VCC") (class "Default")
      (node (ref "+5V") (pin "1") (pinfunction "1_1") (pintype "passive"))
      (node (ref "C15") (pin "2") (pinfunction "2_2") (pintype "passive"))
      (node (ref "C16") (pin "2") (pinfunction "2_2") (pintype "passive"))
      (node (ref "C4") (pin "2") (pinfunction "2_2") (pintype "passive"))
      (node (ref "C5") (pin "+") (pinfunction "+_+") (pintype "passive"))
      (node (ref "C6") (pin "2") (pinfunction "2_2") (pintype "passive"))
      (node (ref "C7") (pin "2") (pinfunction "2_2") (pintype "passive"))
      (node (ref "C8") (pin "2") (pinfunction "2_2") (pintype "passive"))
      (node (ref "IC1") (pin "21") (pinfunction "VCC_21") (pintype "power_in"))
      (node (ref "IC1") (pin "3") (pinfunction "UVCC_3") (pintype "power_in"))
      (node (ref "IC1") (pin "52") (pinfunction "VCC_52") (pintype "power_in"))
      (node (ref "IC1") (pin "64") (pinfunction "AVCC_64") (pintype "power_in"))
      (node (ref "IC1") (pin "8") (pinfunction "VBUS_8") (pintype "bidirectional"))
      (node (ref "LED") (pin "4") (pinfunction "4_4") (pintype "bidirectional"))
      (node (ref "R1") (pin "1") (pinfunction "1_1") (pintype "passive"))
      (node (ref "R2") (pin "1") (pinfunction "1_1") (pintype "passive"))
      (node (ref "R5") (pin "2") (pinfunction "2_2") (pintype "passive"))
      (node (ref "R6") (pin "1") (pinfunction "1_1") (pintype "passive"))
      (node (ref "R7") (pin "2") (pinfunction "2_2") (pintype "passive"))
      (node (ref "R8") (pin "2") (pinfunction "2_2") (pintype "passive"))
      (node (ref "R9") (pin "2") (pinfunction "2_2") (pintype "passive"))
      (node (ref "SER") (pin "TIP") (pinfunction "TIP_TIP") (pintype "bidirectional"))
      (node (ref "U1") (pin "2") (pinfunction "VCC_2") (pintype "power_in"))
      (node (ref "USB") (pin "1") (pinfunction "VCC_1") (pintype "bidirectional"))
    )
    (net (code "85") (name "unconnected-(BL-Pad3)") (class "Default")
      (node (ref "BL") (pin "3") (pinfunction "3_3") (pintype "bidirectional"))
    )
    (net (code "86") (name "unconnected-(IC1-PE1_{slash}RD-Pad34)") (class "Default")
      (node (ref "IC1") (pin "34") (pinfunction "PE1_/RD_34") (pintype "bidirectional"))
    )
    (net (code "87") (name "unconnected-(IC1-PE3_IUID-Pad9)") (class "Default")
      (node (ref "IC1") (pin "9") (pinfunction "PE3_IUID_9") (pintype "bidirectional"))
    )
    (net (code "88") (name "unconnected-(RST-Pad3)") (class "Default")
      (node (ref "RST") (pin "3") (pinfunction "3_3") (pintype "bidirectional"))
    )
    (net (code "89") (name "unconnected-(U$1-Pad8)") (class "Default")
      (node (ref "U$1") (pin "8") (pinfunction "8_8") (pintype "bidirectional"))
    )
    (net (code "90") (name "unconnected-(U1-IN-Pad17)") (class "Default")
      (node (ref "U1") (pin "17") (pinfunction "IN_17") (pintype "bidirectional"))
    )
    (net (code "91") (name "unconnected-(USB-ID-Pad4)") (class "Default")
      (node (ref "USB") (pin "4") (pinfunction "ID_4") (pintype "bidirectional"))
    )
  )
)
